# contact_control_board.net
KiCad netlist of a schematic drawn in EAGLE
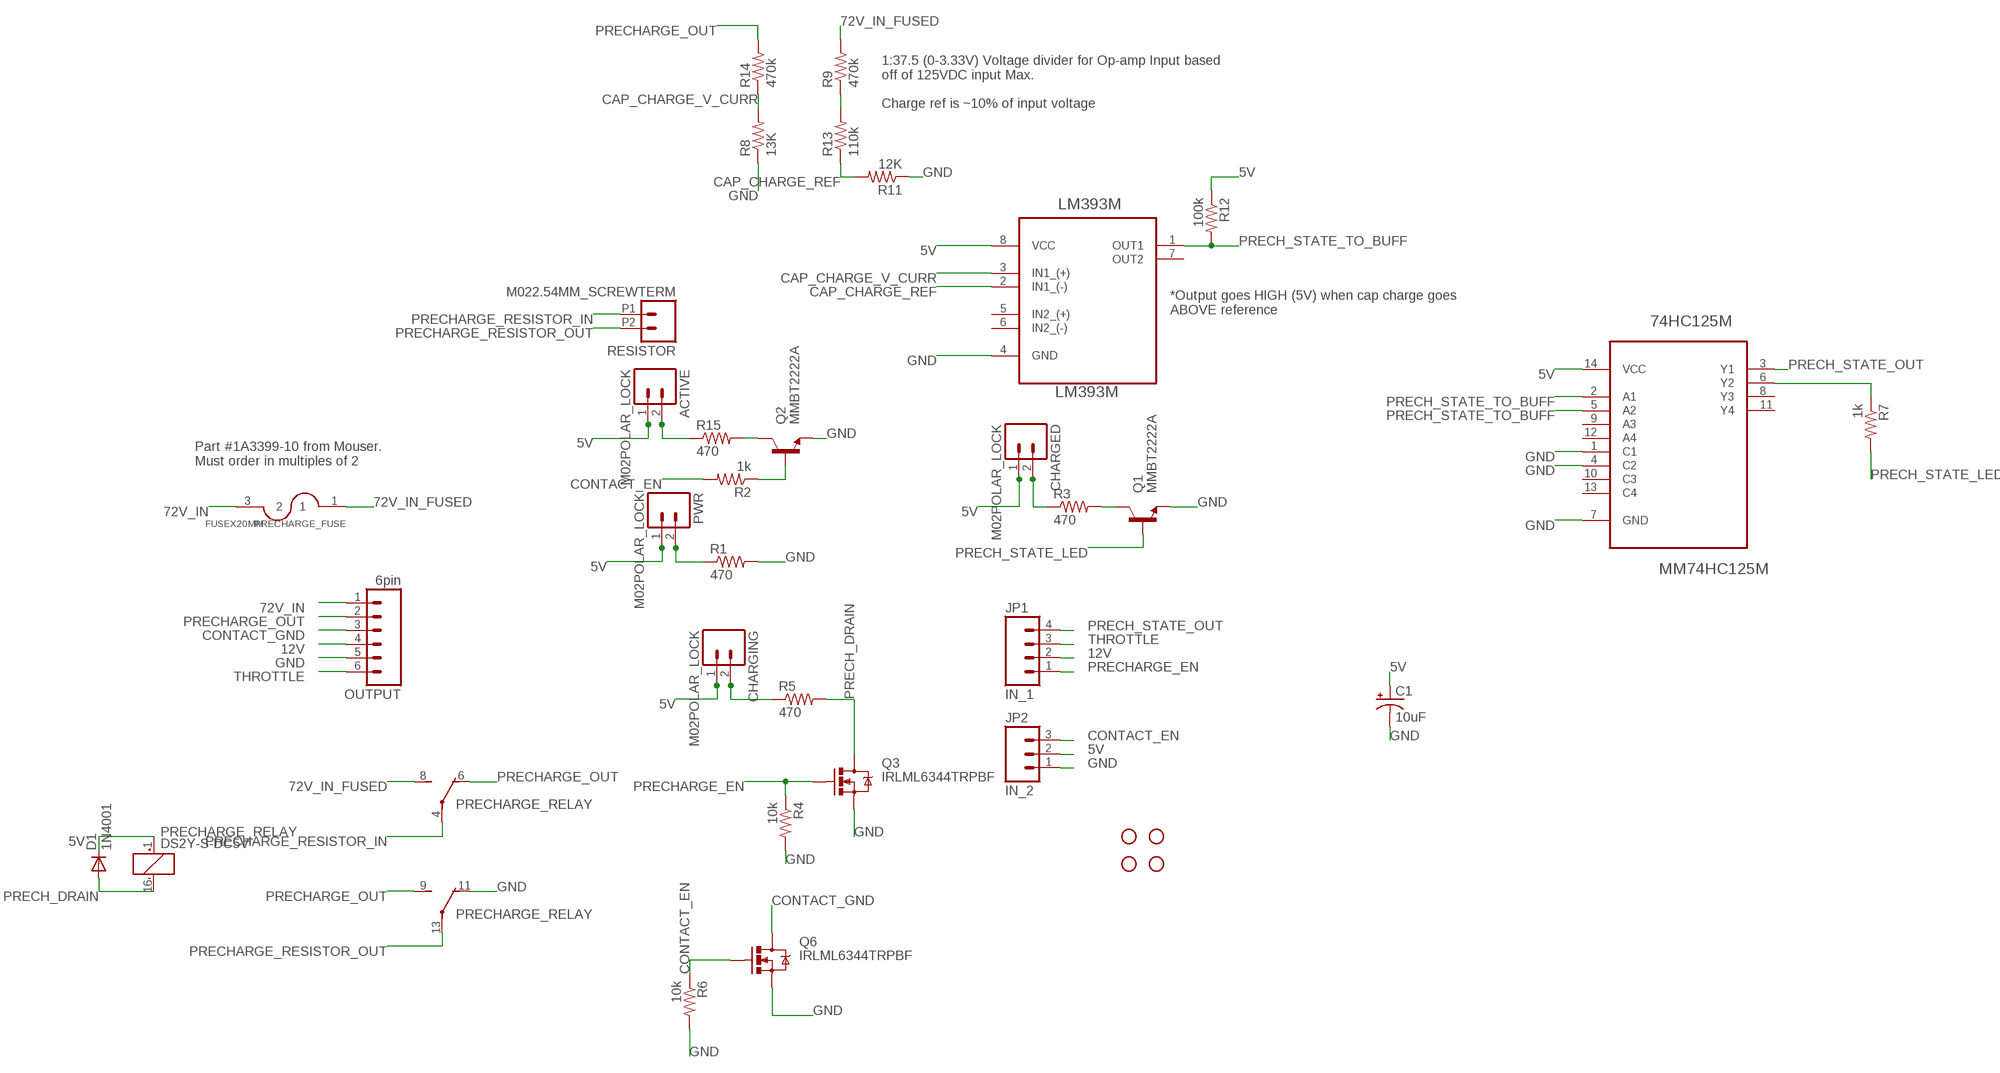
[diagram p0: schematic, sheet 1]

(export (version "E")
  (design (tool "Eeschema 10.0.6"))
  (components
    (comp (ref "74HC125M")
      (value "MM74HC125M")
      (footprint "eagle-import:SOIC127P600X175-14N")
      (libsource (lib "eagle-import") (part "MM74HC125M"))
    )
    (comp (ref "ACTIVE")
      (value "M02POLAR_LOCK")
      (footprint "eagle-import:MOLEX-1X2_LOCK")
      (libsource (lib "eagle-import") (part "M02POLAR_LOCK"))
    )
    (comp (ref "C1")
      (value "10uF")
      (footprint "eagle-import:CPOL-RADIAL-10UF-25V")
      (libsource (lib "eagle-import") (part "CAP_POLPTH2"))
    )
    (comp (ref "CHARGED")
      (value "M02POLAR_LOCK")
      (footprint "eagle-import:MOLEX-1X2_LOCK")
      (libsource (lib "eagle-import") (part "M02POLAR_LOCK"))
    )
    (comp (ref "CHARGING")
      (value "M02POLAR_LOCK")
      (footprint "eagle-import:MOLEX-1X2_LOCK")
      (libsource (lib "eagle-import") (part "M02POLAR_LOCK"))
    )
    (comp (ref "D1")
      (value "1N4001")
      (footprint "eagle-import:DIODE-1N4001")
      (libsource (lib "eagle-import") (part "DIODEPTH"))
    )
    (comp (ref "JP1")
      (value "IN_1")
      (footprint "eagle-import:MOLEX-1X4_LOCK")
      (libsource (lib "eagle-import") (part "M04POLAR_LOCK"))
    )
    (comp (ref "JP2")
      (value "IN_2")
      (footprint "eagle-import:MOLEX-1X3_LOCK")
      (libsource (lib "eagle-import") (part "M03POLAR_LOCK"))
    )
    (comp (ref "LM393M")
      (value "LM393M")
      (footprint "eagle-import:SOIC127P600X180-8N")
      (libsource (lib "eagle-import") (part "LM393M"))
    )
    (comp (ref "OUTPUT")
      (value "6pin")
      (footprint "eagle-import:SCREWTERMINAL-3.5MM-6")
      (libsource (lib "eagle-import") (part "M063.5MM-6"))
    )
    (comp (ref "PRECHARGE_FUSE")
      (value "FUSEX20MM")
      (footprint "eagle-import:FUSE_5MM")
      (libsource (lib "eagle-import") (part "FUSEX20MM"))
    )
    (comp (ref "PRECHARGE_RELAY")
      (value "DS2Y-S-DC5V")
      (footprint "eagle-import:DS2Y")
      (libsource (lib "eagle-import") (part "DS2Y-S-DC5V"))
    )
    (comp (ref "PWR")
      (value "M02POLAR_LOCK")
      (footprint "eagle-import:MOLEX-1X2_LOCK")
      (libsource (lib "eagle-import") (part "M02POLAR_LOCK"))
    )
    (comp (ref "Q1")
      (value "MMBT2222A")
      (footprint "eagle-import:SOT23")
      (libsource (lib "eagle-import") (part "TRANSISTOR_NPNMMBT2222A"))
    )
    (comp (ref "Q2")
      (value "MMBT2222A")
      (footprint "eagle-import:SOT23")
      (libsource (lib "eagle-import") (part "TRANSISTOR_NPNMMBT2222A"))
    )
    (comp (ref "Q3")
      (value "IRLML6344TRPBF")
      (footprint "eagle-import:SOT23")
      (libsource (lib "eagle-import") (part "MOSFET-NCHANNELBSS123LT1G"))
    )
    (comp (ref "Q6")
      (value "IRLML6344TRPBF")
      (footprint "eagle-import:SOT23")
      (libsource (lib "eagle-import") (part "MOSFET-NCHANNELBSS123LT1G"))
    )
    (comp (ref "R1")
      (value "470")
      (footprint "eagle-import:0805")
      (libsource (lib "eagle-import") (part "RESISTOR0805-RES"))
    )
    (comp (ref "R2")
      (value "1k")
      (footprint "eagle-import:0603-RES")
      (libsource (lib "eagle-import") (part "RESISTOR0603-RES"))
    )
    (comp (ref "R3")
      (value "470")
      (footprint "eagle-import:0805")
      (libsource (lib "eagle-import") (part "RESISTOR0805-RES"))
    )
    (comp (ref "R4")
      (value "10k")
      (footprint "eagle-import:0603-RES")
      (libsource (lib "eagle-import") (part "RESISTOR0603-RES"))
    )
    (comp (ref "R5")
      (value "470")
      (footprint "eagle-import:0805")
      (libsource (lib "eagle-import") (part "RESISTOR0805-RES"))
    )
    (comp (ref "R6")
      (value "10k")
      (footprint "eagle-import:0603-RES")
      (libsource (lib "eagle-import") (part "RESISTOR0603-RES"))
    )
    (comp (ref "R7")
      (value "1k")
      (footprint "eagle-import:0603-RES")
      (libsource (lib "eagle-import") (part "RESISTOR0603-RES"))
    )
    (comp (ref "R8")
      (value "13K")
      (footprint "eagle-import:0805")
      (libsource (lib "eagle-import") (part "RESISTOR0805-RES"))
    )
    (comp (ref "R9")
      (value "470k")
      (footprint "eagle-import:0805")
      (libsource (lib "eagle-import") (part "RESISTOR0805-RES"))
    )
    (comp (ref "R11")
      (value "12K")
      (footprint "eagle-import:0805")
      (libsource (lib "eagle-import") (part "RESISTOR0805-RES"))
    )
    (comp (ref "R12")
      (value "100k")
      (footprint "eagle-import:0603-RES")
      (libsource (lib "eagle-import") (part "RESISTOR0603-RES"))
    )
    (comp (ref "R13")
      (value "110k")
      (footprint "eagle-import:0805")
      (libsource (lib "eagle-import") (part "RESISTOR0805-RES"))
    )
    (comp (ref "R14")
      (value "470k")
      (footprint "eagle-import:0805")
      (libsource (lib "eagle-import") (part "RESISTOR0805-RES"))
    )
    (comp (ref "R15")
      (value "470")
      (footprint "eagle-import:0805")
      (libsource (lib "eagle-import") (part "RESISTOR0805-RES"))
    )
    (comp (ref "RESISTOR")
      (value "M022.54MM_SCREWTERM")
      (footprint "eagle-import:1X02_2.54_SCREWTERM")
      (libsource (lib "eagle-import") (part "M022.54MM_SCREWTERM"))
    )
    (comp (ref "STANDOFF1")
      (value "STAND-OFF")
      (footprint "eagle-import:STAND-OFF")
      (libsource (lib "eagle-import") (part "STAND-OFF"))
    )
    (comp (ref "STANDOFF2")
      (value "STAND-OFF")
      (footprint "eagle-import:STAND-OFF")
      (libsource (lib "eagle-import") (part "STAND-OFF"))
    )
    (comp (ref "STANDOFF3")
      (value "STAND-OFF")
      (footprint "eagle-import:STAND-OFF")
      (libsource (lib "eagle-import") (part "STAND-OFF"))
    )
    (comp (ref "STANDOFF4")
      (value "STAND-OFF")
      (footprint "eagle-import:STAND-OFF")
      (libsource (lib "eagle-import") (part "STAND-OFF"))
    )
  )
  (nets
    (net (code "1") (name "/5V") (class "Default")
      (node (ref "74HC125M") (pin "14") (pinfunction "VCC_14") (pintype "power_in"))
      (node (ref "ACTIVE") (pin "1") (pinfunction "1_1") (pintype "passive"))
      (node (ref "C1") (pin "1") (pinfunction "+_1") (pintype "passive"))
      (node (ref "CHARGED") (pin "1") (pinfunction "1_1") (pintype "passive"))
      (node (ref "CHARGING") (pin "1") (pinfunction "1_1") (pintype "passive"))
      (node (ref "D1") (pin "C") (pinfunction "C_C") (pintype "passive"))
      (node (ref "JP2") (pin "2") (pinfunction "2_2") (pintype "passive"))
      (node (ref "LM393M") (pin "8") (pinfunction "VCC_8") (pintype "power_in"))
      (node (ref "PRECHARGE_RELAY") (pin "1") (pinfunction "+_1") (pintype "passive"))
      (node (ref "PWR") (pin "1") (pinfunction "1_1") (pintype "passive"))
      (node (ref "R12") (pin "1") (pinfunction "1_1") (pintype "passive"))
    )
    (net (code "2") (name "/12V") (class "Default")
      (node (ref "JP1") (pin "2") (pinfunction "2_2") (pintype "passive"))
      (node (ref "OUTPUT") (pin "4") (pinfunction "4_4") (pintype "passive"))
    )
    (net (code "3") (name "/72V_IN") (class "Default")
      (node (ref "OUTPUT") (pin "1") (pinfunction "1_1") (pintype "passive"))
      (node (ref "PRECHARGE_FUSE") (pin "3") (pinfunction "2_3") (pintype "bidirectional"))
    )
    (net (code "4") (name "/72V_IN_FUSED") (class "Default")
      (node (ref "PRECHARGE_FUSE") (pin "1") (pinfunction "1_1") (pintype "bidirectional"))
      (node (ref "PRECHARGE_RELAY") (pin "8") (pinfunction "S_8") (pintype "passive"))
      (node (ref "R9") (pin "2") (pinfunction "2_2") (pintype "passive"))
    )
    (net (code "5") (name "/CAP_CHARGE_REF") (class "Default")
      (node (ref "LM393M") (pin "2") (pinfunction "IN1_(-)_2") (pintype "input"))
      (node (ref "R11") (pin "2") (pinfunction "2_2") (pintype "passive"))
      (node (ref "R13") (pin "1") (pinfunction "1_1") (pintype "passive"))
    )
    (net (code "6") (name "/CAP_CHARGE_V_CURR") (class "Default")
      (node (ref "LM393M") (pin "3") (pinfunction "IN1_(+)_3") (pintype "input"))
      (node (ref "R14") (pin "1") (pinfunction "1_1") (pintype "passive"))
      (node (ref "R8") (pin "2") (pinfunction "2_2") (pintype "passive"))
    )
    (net (code "7") (name "/CONTACT_EN") (class "Default")
      (node (ref "JP2") (pin "3") (pinfunction "3_3") (pintype "passive"))
      (node (ref "Q6") (pin "1") (pinfunction "G_1") (pintype "passive"))
      (node (ref "R2") (pin "2") (pinfunction "2_2") (pintype "passive"))
      (node (ref "R6") (pin "1") (pinfunction "1_1") (pintype "passive"))
    )
    (net (code "8") (name "/CONTACT_GND") (class "Default")
      (node (ref "OUTPUT") (pin "3") (pinfunction "3_3") (pintype "passive"))
      (node (ref "Q6") (pin "3") (pinfunction "D_3") (pintype "passive"))
    )
    (net (code "9") (name "/GND") (class "Default")
      (node (ref "74HC125M") (pin "1") (pinfunction "C1_1") (pintype "input"))
      (node (ref "74HC125M") (pin "4") (pinfunction "C2_4") (pintype "input"))
      (node (ref "74HC125M") (pin "7") (pinfunction "GND_7") (pintype "passive"))
      (node (ref "C1") (pin "2") (pinfunction "-_2") (pintype "passive"))
      (node (ref "JP2") (pin "1") (pinfunction "1_1") (pintype "passive"))
      (node (ref "LM393M") (pin "4") (pinfunction "GND_4") (pintype "passive"))
      (node (ref "OUTPUT") (pin "5") (pinfunction "5_5") (pintype "passive"))
      (node (ref "PRECHARGE_RELAY") (pin "11") (pinfunction "O_11") (pintype "passive"))
      (node (ref "Q1") (pin "2") (pinfunction "E_2") (pintype "passive"))
      (node (ref "Q2") (pin "2") (pinfunction "E_2") (pintype "passive"))
      (node (ref "Q3") (pin "2") (pinfunction "S_2") (pintype "passive"))
      (node (ref "Q6") (pin "2") (pinfunction "S_2") (pintype "passive"))
      (node (ref "R1") (pin "2") (pinfunction "2_2") (pintype "passive"))
      (node (ref "R11") (pin "1") (pinfunction "1_1") (pintype "passive"))
      (node (ref "R4") (pin "2") (pinfunction "2_2") (pintype "passive"))
      (node (ref "R6") (pin "2") (pinfunction "2_2") (pintype "passive"))
      (node (ref "R8") (pin "1") (pinfunction "1_1") (pintype "passive"))
    )
    (net (code "10") (name "/PRECHARGE_EN") (class "Default")
      (node (ref "JP1") (pin "1") (pinfunction "1_1") (pintype "passive"))
      (node (ref "Q3") (pin "1") (pinfunction "G_1") (pintype "passive"))
      (node (ref "R4") (pin "1") (pinfunction "1_1") (pintype "passive"))
    )
    (net (code "11") (name "/PRECHARGE_OUT") (class "Default")
      (node (ref "OUTPUT") (pin "2") (pinfunction "2_2") (pintype "passive"))
      (node (ref "PRECHARGE_RELAY") (pin "6") (pinfunction "O_6") (pintype "passive"))
      (node (ref "PRECHARGE_RELAY") (pin "9") (pinfunction "S_9") (pintype "passive"))
      (node (ref "R14") (pin "2") (pinfunction "2_2") (pintype "passive"))
    )
    (net (code "12") (name "/PRECHARGE_RESISTOR_IN") (class "Default")
      (node (ref "PRECHARGE_RELAY") (pin "4") (pinfunction "P_4") (pintype "passive"))
      (node (ref "RESISTOR") (pin "P1") (pinfunction "1_P1") (pintype "passive"))
    )
    (net (code "13") (name "/PRECHARGE_RESISTOR_OUT") (class "Default")
      (node (ref "PRECHARGE_RELAY") (pin "13") (pinfunction "P_13") (pintype "passive"))
      (node (ref "RESISTOR") (pin "P2") (pinfunction "2_P2") (pintype "passive"))
    )
    (net (code "14") (name "/PRECH_DRAIN") (class "Default")
      (node (ref "D1") (pin "A") (pinfunction "A_A") (pintype "passive"))
      (node (ref "PRECHARGE_RELAY") (pin "16") (pinfunction "-_16") (pintype "passive"))
      (node (ref "Q3") (pin "3") (pinfunction "D_3") (pintype "passive"))
      (node (ref "R5") (pin "2") (pinfunction "2_2") (pintype "passive"))
    )
    (net (code "15") (name "/PRECH_STATE_LED") (class "Default")
      (node (ref "Q1") (pin "1") (pinfunction "B_1") (pintype "passive"))
      (node (ref "R7") (pin "2") (pinfunction "2_2") (pintype "passive"))
    )
    (net (code "16") (name "/PRECH_STATE_OUT") (class "Default")
      (node (ref "74HC125M") (pin "3") (pinfunction "Y1_3") (pintype "output"))
      (node (ref "JP1") (pin "4") (pinfunction "4_4") (pintype "passive"))
    )
    (net (code "17") (name "/PRECH_STATE_TO_BUFF") (class "Default")
      (node (ref "74HC125M") (pin "2") (pinfunction "A1_2") (pintype "input"))
      (node (ref "74HC125M") (pin "5") (pinfunction "A2_5") (pintype "input"))
      (node (ref "LM393M") (pin "1") (pinfunction "OUT1_1") (pintype "output"))
      (node (ref "R12") (pin "2") (pinfunction "2_2") (pintype "passive"))
    )
    (net (code "18") (name "/THROTTLE") (class "Default")
      (node (ref "JP1") (pin "3") (pinfunction "3_3") (pintype "passive"))
      (node (ref "OUTPUT") (pin "6") (pinfunction "6_6") (pintype "passive"))
    )
    (net (code "19") (name "Net-(74HC125M-Y2)") (class "Default")
      (node (ref "74HC125M") (pin "6") (pinfunction "Y2_6") (pintype "output"))
      (node (ref "R7") (pin "1") (pinfunction "1_1") (pintype "passive"))
    )
    (net (code "20") (name "Net-(ACTIVE-Pad2)") (class "Default")
      (node (ref "ACTIVE") (pin "2") (pinfunction "2_2") (pintype "passive"))
      (node (ref "R15") (pin "1") (pinfunction "1_1") (pintype "passive"))
    )
    (net (code "21") (name "Net-(CHARGED-Pad2)") (class "Default")
      (node (ref "CHARGED") (pin "2") (pinfunction "2_2") (pintype "passive"))
      (node (ref "R3") (pin "1") (pinfunction "1_1") (pintype "passive"))
    )
    (net (code "22") (name "Net-(CHARGING-Pad2)") (class "Default")
      (node (ref "CHARGING") (pin "2") (pinfunction "2_2") (pintype "passive"))
      (node (ref "R5") (pin "1") (pinfunction "1_1") (pintype "passive"))
    )
    (net (code "23") (name "Net-(PWR-Pad2)") (class "Default")
      (node (ref "PWR") (pin "2") (pinfunction "2_2") (pintype "passive"))
      (node (ref "R1") (pin "1") (pinfunction "1_1") (pintype "passive"))
    )
    (net (code "24") (name "Net-(Q1-C)") (class "Default")
      (node (ref "Q1") (pin "3") (pinfunction "C_3") (pintype "passive"))
      (node (ref "R3") (pin "2") (pinfunction "2_2") (pintype "passive"))
    )
    (net (code "25") (name "Net-(Q2-B)") (class "Default")
      (node (ref "Q2") (pin "1") (pinfunction "B_1") (pintype "passive"))
      (node (ref "R2") (pin "1") (pinfunction "1_1") (pintype "passive"))
    )
    (net (code "26") (name "Net-(Q2-C)") (class "Default")
      (node (ref "Q2") (pin "3") (pinfunction "C_3") (pintype "passive"))
      (node (ref "R15") (pin "2") (pinfunction "2_2") (pintype "passive"))
    )
    (net (code "27") (name "Net-(R13-Pad2)") (class "Default")
      (node (ref "R13") (pin "2") (pinfunction "2_2") (pintype "passive"))
      (node (ref "R9") (pin "1") (pinfunction "1_1") (pintype "passive"))
    )
    (net (code "28") (name "unconnected-(74HC125M-A3-Pad9)") (class "Default")
      (node (ref "74HC125M") (pin "9") (pinfunction "A3_9") (pintype "input"))
    )
    (net (code "29") (name "unconnected-(74HC125M-A4-Pad12)") (class "Default")
      (node (ref "74HC125M") (pin "12") (pinfunction "A4_12") (pintype "input"))
    )
    (net (code "30") (name "unconnected-(74HC125M-C3-Pad10)") (class "Default")
      (node (ref "74HC125M") (pin "10") (pinfunction "C3_10") (pintype "input"))
    )
    (net (code "31") (name "unconnected-(74HC125M-C4-Pad13)") (class "Default")
      (node (ref "74HC125M") (pin "13") (pinfunction "C4_13") (pintype "input"))
    )
    (net (code "32") (name "unconnected-(74HC125M-Y3-Pad8)") (class "Default")
      (node (ref "74HC125M") (pin "8") (pinfunction "Y3_8") (pintype "output"))
    )
    (net (code "33") (name "unconnected-(74HC125M-Y4-Pad11)") (class "Default")
      (node (ref "74HC125M") (pin "11") (pinfunction "Y4_11") (pintype "output"))
    )
    (net (code "34") (name "unconnected-(LM393M-IN2_(+)-Pad5)") (class "Default")
      (node (ref "LM393M") (pin "5") (pinfunction "IN2_(+)_5") (pintype "input"))
    )
    (net (code "35") (name "unconnected-(LM393M-IN2_(-)-Pad6)") (class "Default")
      (node (ref "LM393M") (pin "6") (pinfunction "IN2_(-)_6") (pintype "input"))
    )
    (net (code "36") (name "unconnected-(LM393M-OUT2-Pad7)") (class "Default")
      (node (ref "LM393M") (pin "7") (pinfunction "OUT2_7") (pintype "output"))
    )
  )
)
